# CPLD.net
KiCad netlist of a schematic drawn in Altium Designer
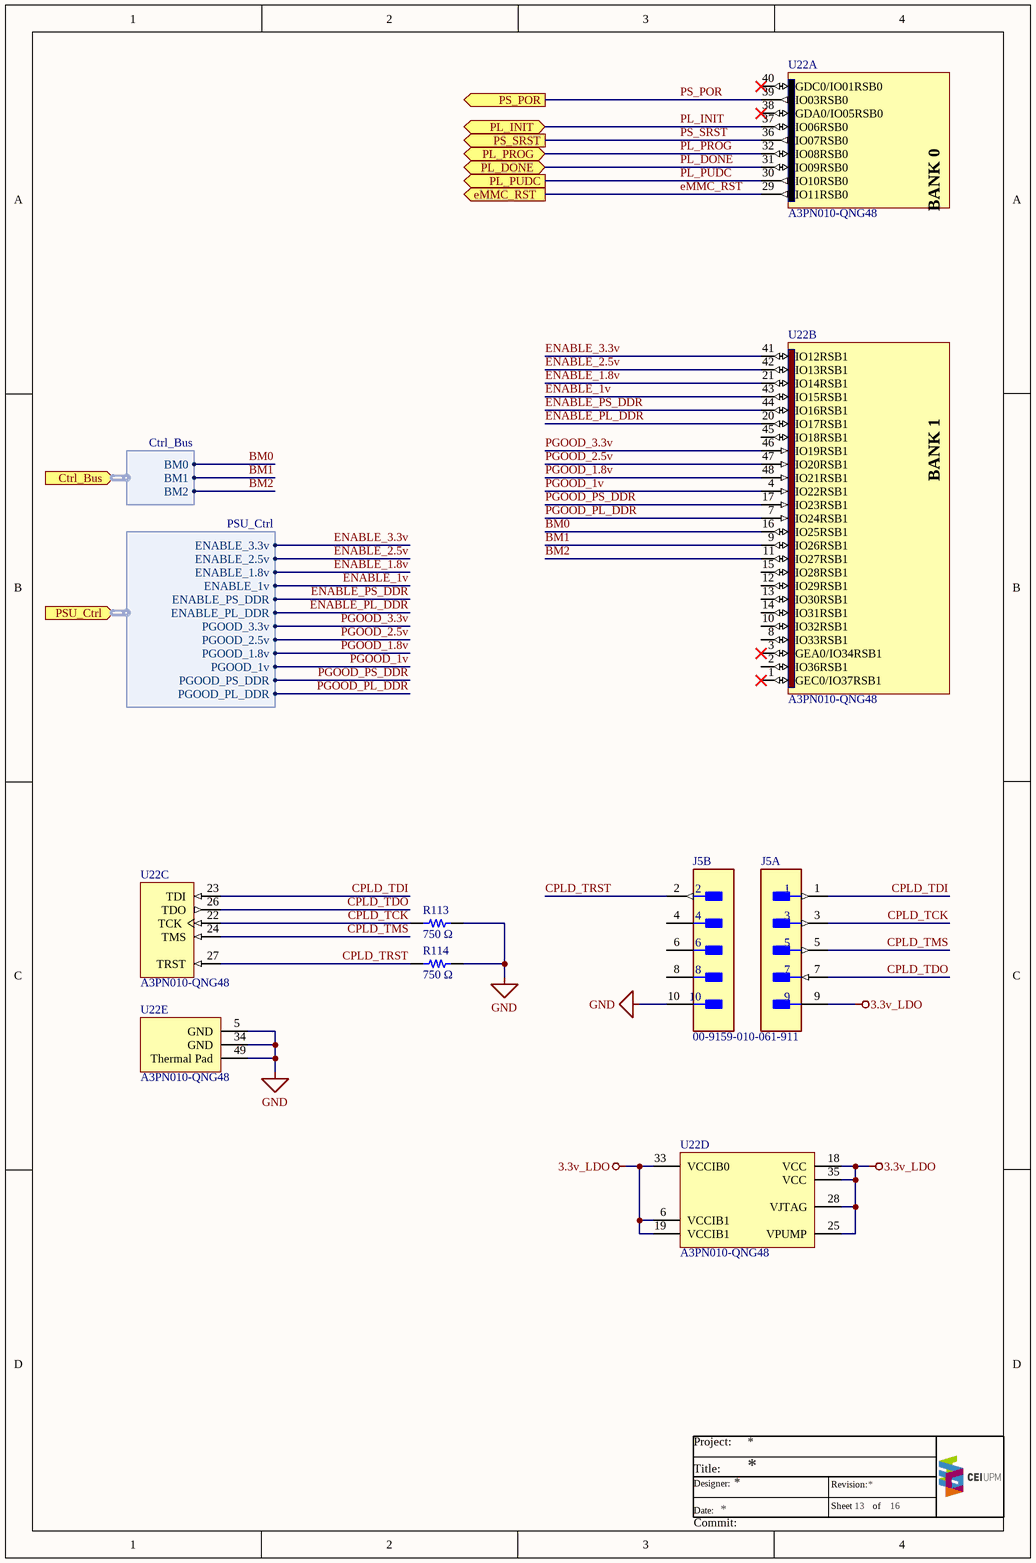
[diagram p0: CPLD.SchDoc]

(export (version "E")
  (design (tool "Eeschema 10.0.6"))
  (components
    (comp (ref "J5")
      (value "00-9159-010-061-911")
      (footprint "KYOCERA_00-9159-010-061-911")
      (description "Coplanar Open Ended Card Edge Connector 10 Pin")
      (libsource (lib "") (part "00-9159-010-061-911_1"))
    )
    (comp (ref "R113")
      (value "750 Ω")
      (footprint "PANASONIC_ERJ2G_0402")
      (description "General Purpose Thick Film Chip Resistors")
      (fields (field (name "MANUFACTURER") "Panasonic"))
      (libsource (lib "SpaceVNX") (part "ERJ2RKF7500X"))
    )
    (comp (ref "R114")
      (value "750 Ω")
      (footprint "PANASONIC_ERJ2G_0402")
      (description "General Purpose Thick Film Chip Resistors")
      (fields (field (name "MANUFACTURER") "Panasonic"))
      (libsource (lib "SpaceVNX") (part "ERJ2RKF7500X"))
    )
    (comp (ref "U22")
      (value "A3PN010-QNG48")
      (footprint "Actel_QN48")
      (libsource (lib "SpaceVNX") (part "A3PN010-QNG48"))
    )
  )
  (nets
    (net (code "3") (name "/BM0") (class "Default")
      (node (ref "U22") (pin "16") (pinfunction "IO25RSB1_16") (pintype "bidirectional"))
    )
    (net (code "4") (name "/BM1") (class "Default")
      (node (ref "U22") (pin "9") (pinfunction "IO26RSB1_9") (pintype "bidirectional"))
    )
    (net (code "5") (name "/BM2") (class "Default")
      (node (ref "U22") (pin "11") (pinfunction "IO27RSB1_11") (pintype "bidirectional"))
    )
    (net (code "6") (name "/CPLD_TCK") (class "Default")
      (node (ref "J5") (pin "3") (pinfunction "3_3") (pintype "output"))
      (node (ref "R113") (pin "1") (pinfunction "1_1") (pintype "passive"))
      (node (ref "U22") (pin "22") (pinfunction "TCK_22") (pintype "input"))
    )
    (net (code "7") (name "/CPLD_TDI") (class "Default")
      (node (ref "J5") (pin "1") (pinfunction "1_1") (pintype "output"))
      (node (ref "U22") (pin "23") (pinfunction "TDI_23") (pintype "input"))
    )
    (net (code "8") (name "/CPLD_TDO") (class "Default")
      (node (ref "J5") (pin "7") (pinfunction "7_7") (pintype "input"))
      (node (ref "U22") (pin "26") (pinfunction "TDO_26") (pintype "output"))
    )
    (net (code "9") (name "/CPLD_TMS") (class "Default")
      (node (ref "J5") (pin "5") (pinfunction "5_5") (pintype "output"))
      (node (ref "U22") (pin "24") (pinfunction "TMS_24") (pintype "input"))
    )
    (net (code "10") (name "/CPLD_TRST") (class "Default")
      (node (ref "J5") (pin "2") (pinfunction "2_2") (pintype "output"))
      (node (ref "R114") (pin "1") (pinfunction "1_1") (pintype "passive"))
      (node (ref "U22") (pin "27") (pinfunction "TRST_27") (pintype "input"))
    )
    (net (code "11") (name "/ENABLE_1.8v") (class "Default")
      (node (ref "U22") (pin "21") (pinfunction "IO14RSB1_21") (pintype "bidirectional"))
    )
    (net (code "12") (name "/ENABLE_1v") (class "Default")
      (node (ref "U22") (pin "43") (pinfunction "IO15RSB1_43") (pintype "bidirectional"))
    )
    (net (code "13") (name "/ENABLE_2.5v") (class "Default")
      (node (ref "U22") (pin "42") (pinfunction "IO13RSB1_42") (pintype "bidirectional"))
    )
    (net (code "14") (name "/ENABLE_3.3v") (class "Default")
      (node (ref "U22") (pin "41") (pinfunction "IO12RSB1_41") (pintype "bidirectional"))
    )
    (net (code "15") (name "/ENABLE_PL_DDR") (class "Default")
      (node (ref "U22") (pin "20") (pinfunction "IO17RSB1_20") (pintype "bidirectional"))
    )
    (net (code "16") (name "/ENABLE_PS_DDR") (class "Default")
      (node (ref "U22") (pin "44") (pinfunction "IO16RSB1_44") (pintype "bidirectional"))
    )
    (net (code "17") (name "/PGOOD_1.8v") (class "Default")
      (node (ref "U22") (pin "48") (pinfunction "IO21RSB1_48") (pintype "bidirectional"))
    )
    (net (code "18") (name "/PGOOD_1v") (class "Default")
      (node (ref "U22") (pin "4") (pinfunction "IO22RSB1_4") (pintype "bidirectional"))
    )
    (net (code "19") (name "/PGOOD_2.5v") (class "Default")
      (node (ref "U22") (pin "47") (pinfunction "IO20RSB1_47") (pintype "bidirectional"))
    )
    (net (code "20") (name "/PGOOD_3.3v") (class "Default")
      (node (ref "U22") (pin "46") (pinfunction "IO19RSB1_46") (pintype "bidirectional"))
    )
    (net (code "21") (name "/PGOOD_PL_DDR") (class "Default")
      (node (ref "U22") (pin "7") (pinfunction "IO24RSB1_7") (pintype "bidirectional"))
    )
    (net (code "22") (name "/PGOOD_PS_DDR") (class "Default")
      (node (ref "U22") (pin "17") (pinfunction "IO23RSB1_17") (pintype "bidirectional"))
    )
    (net (code "23") (name "/PL_DONE") (class "Default")
      (node (ref "U22") (pin "31") (pinfunction "IO09RSB0_31") (pintype "bidirectional"))
    )
    (net (code "24") (name "/PL_INIT") (class "Default")
      (node (ref "U22") (pin "37") (pinfunction "IO06RSB0_37") (pintype "bidirectional"))
    )
    (net (code "25") (name "/PL_PROG") (class "Default")
      (node (ref "U22") (pin "32") (pinfunction "IO08RSB0_32") (pintype "bidirectional"))
    )
    (net (code "26") (name "/PL_PUDC") (class "Default")
      (node (ref "U22") (pin "30") (pinfunction "IO10RSB0_30") (pintype "output"))
    )
    (net (code "27") (name "/PS_POR") (class "Default")
      (node (ref "U22") (pin "39") (pinfunction "IO03RSB0_39") (pintype "output"))
    )
    (net (code "28") (name "/PS_SRST") (class "Default")
      (node (ref "U22") (pin "36") (pinfunction "IO07RSB0_36") (pintype "output"))
    )
    (net (code "29") (name "/eMMC_RST") (class "Default")
      (node (ref "U22") (pin "29") (pinfunction "IO11RSB0_29") (pintype "output"))
    )
    (net (code "32") (name "3.3v_LDO") (class "Default")
      (node (ref "J5") (pin "9") (pinfunction "9_9") (pintype "power_in"))
      (node (ref "U22") (pin "18") (pinfunction "VCC_18") (pintype "power_in"))
      (node (ref "U22") (pin "19") (pinfunction "VCCIB1_19") (pintype "power_in"))
      (node (ref "U22") (pin "25") (pinfunction "VPUMP_25") (pintype "power_in"))
      (node (ref "U22") (pin "28") (pinfunction "VJTAG_28") (pintype "power_in"))
      (node (ref "U22") (pin "33") (pinfunction "VCCIB0_33") (pintype "power_in"))
      (node (ref "U22") (pin "35") (pinfunction "VCC_35") (pintype "power_in"))
      (node (ref "U22") (pin "6") (pinfunction "VCCIB1_6") (pintype "power_in"))
    )
    (net (code "33") (name "GND") (class "Default")
      (node (ref "J5") (pin "10") (pinfunction "10_10") (pintype "passive"))
      (node (ref "R113") (pin "2") (pinfunction "2_2") (pintype "passive"))
      (node (ref "R114") (pin "2") (pinfunction "2_2") (pintype "passive"))
      (node (ref "U22") (pin "34") (pinfunction "GND_34") (pintype "power_in"))
      (node (ref "U22") (pin "49") (pinfunction "Thermal_Pad_49") (pintype "power_in"))
      (node (ref "U22") (pin "5") (pinfunction "GND_5") (pintype "power_in"))
    )
    (net (code "34") (name "unconnected-(J5-Pad4)") (class "Default")
      (node (ref "J5") (pin "4") (pinfunction "4_4") (pintype "passive"))
    )
    (net (code "35") (name "unconnected-(J5-Pad6)") (class "Default")
      (node (ref "J5") (pin "6") (pinfunction "6_6") (pintype "passive"))
    )
    (net (code "36") (name "unconnected-(J5-Pad8)") (class "Default")
      (node (ref "J5") (pin "8") (pinfunction "8_8") (pintype "passive"))
    )
    (net (code "37") (name "unconnected-(U22A-GDA0{slash}IO05RSB0-Pad38)") (class "Default")
      (node (ref "U22") (pin "38") (pinfunction "GDA0/IO05RSB0_38") (pintype "bidirectional+no_connect"))
    )
    (net (code "38") (name "unconnected-(U22A-GDC0{slash}IO01RSB0-Pad40)") (class "Default")
      (node (ref "U22") (pin "40") (pinfunction "GDC0/IO01RSB0_40") (pintype "bidirectional+no_connect"))
    )
    (net (code "39") (name "unconnected-(U22B-GEA0{slash}IO34RSB1-Pad3)") (class "Default")
      (node (ref "U22") (pin "3") (pinfunction "GEA0/IO34RSB1_3") (pintype "bidirectional+no_connect"))
    )
    (net (code "40") (name "unconnected-(U22B-GEC0{slash}IO37RSB1-Pad1)") (class "Default")
      (node (ref "U22") (pin "1") (pinfunction "GEC0/IO37RSB1_1") (pintype "bidirectional+no_connect"))
    )
    (net (code "41") (name "unconnected-(U22B-IO18RSB1-Pad45)") (class "Default")
      (node (ref "U22") (pin "45") (pinfunction "IO18RSB1_45") (pintype "bidirectional"))
    )
    (net (code "42") (name "unconnected-(U22B-IO28RSB1-Pad15)") (class "Default")
      (node (ref "U22") (pin "15") (pinfunction "IO28RSB1_15") (pintype "bidirectional"))
    )
    (net (code "43") (name "unconnected-(U22B-IO29RSB1-Pad12)") (class "Default")
      (node (ref "U22") (pin "12") (pinfunction "IO29RSB1_12") (pintype "bidirectional"))
    )
    (net (code "44") (name "unconnected-(U22B-IO30RSB1-Pad13)") (class "Default")
      (node (ref "U22") (pin "13") (pinfunction "IO30RSB1_13") (pintype "bidirectional"))
    )
    (net (code "45") (name "unconnected-(U22B-IO31RSB1-Pad14)") (class "Default")
      (node (ref "U22") (pin "14") (pinfunction "IO31RSB1_14") (pintype "bidirectional"))
    )
    (net (code "46") (name "unconnected-(U22B-IO32RSB1-Pad10)") (class "Default")
      (node (ref "U22") (pin "10") (pinfunction "IO32RSB1_10") (pintype "bidirectional"))
    )
    (net (code "47") (name "unconnected-(U22B-IO33RSB1-Pad8)") (class "Default")
      (node (ref "U22") (pin "8") (pinfunction "IO33RSB1_8") (pintype "bidirectional"))
    )
    (net (code "48") (name "unconnected-(U22B-IO36RSB1-Pad2)") (class "Default")
      (node (ref "U22") (pin "2") (pinfunction "IO36RSB1_2") (pintype "bidirectional"))
    )
  )
)
